# Un_Zigbee_V1_0.net
KiCad netlist of a schematic drawn in EAGLE
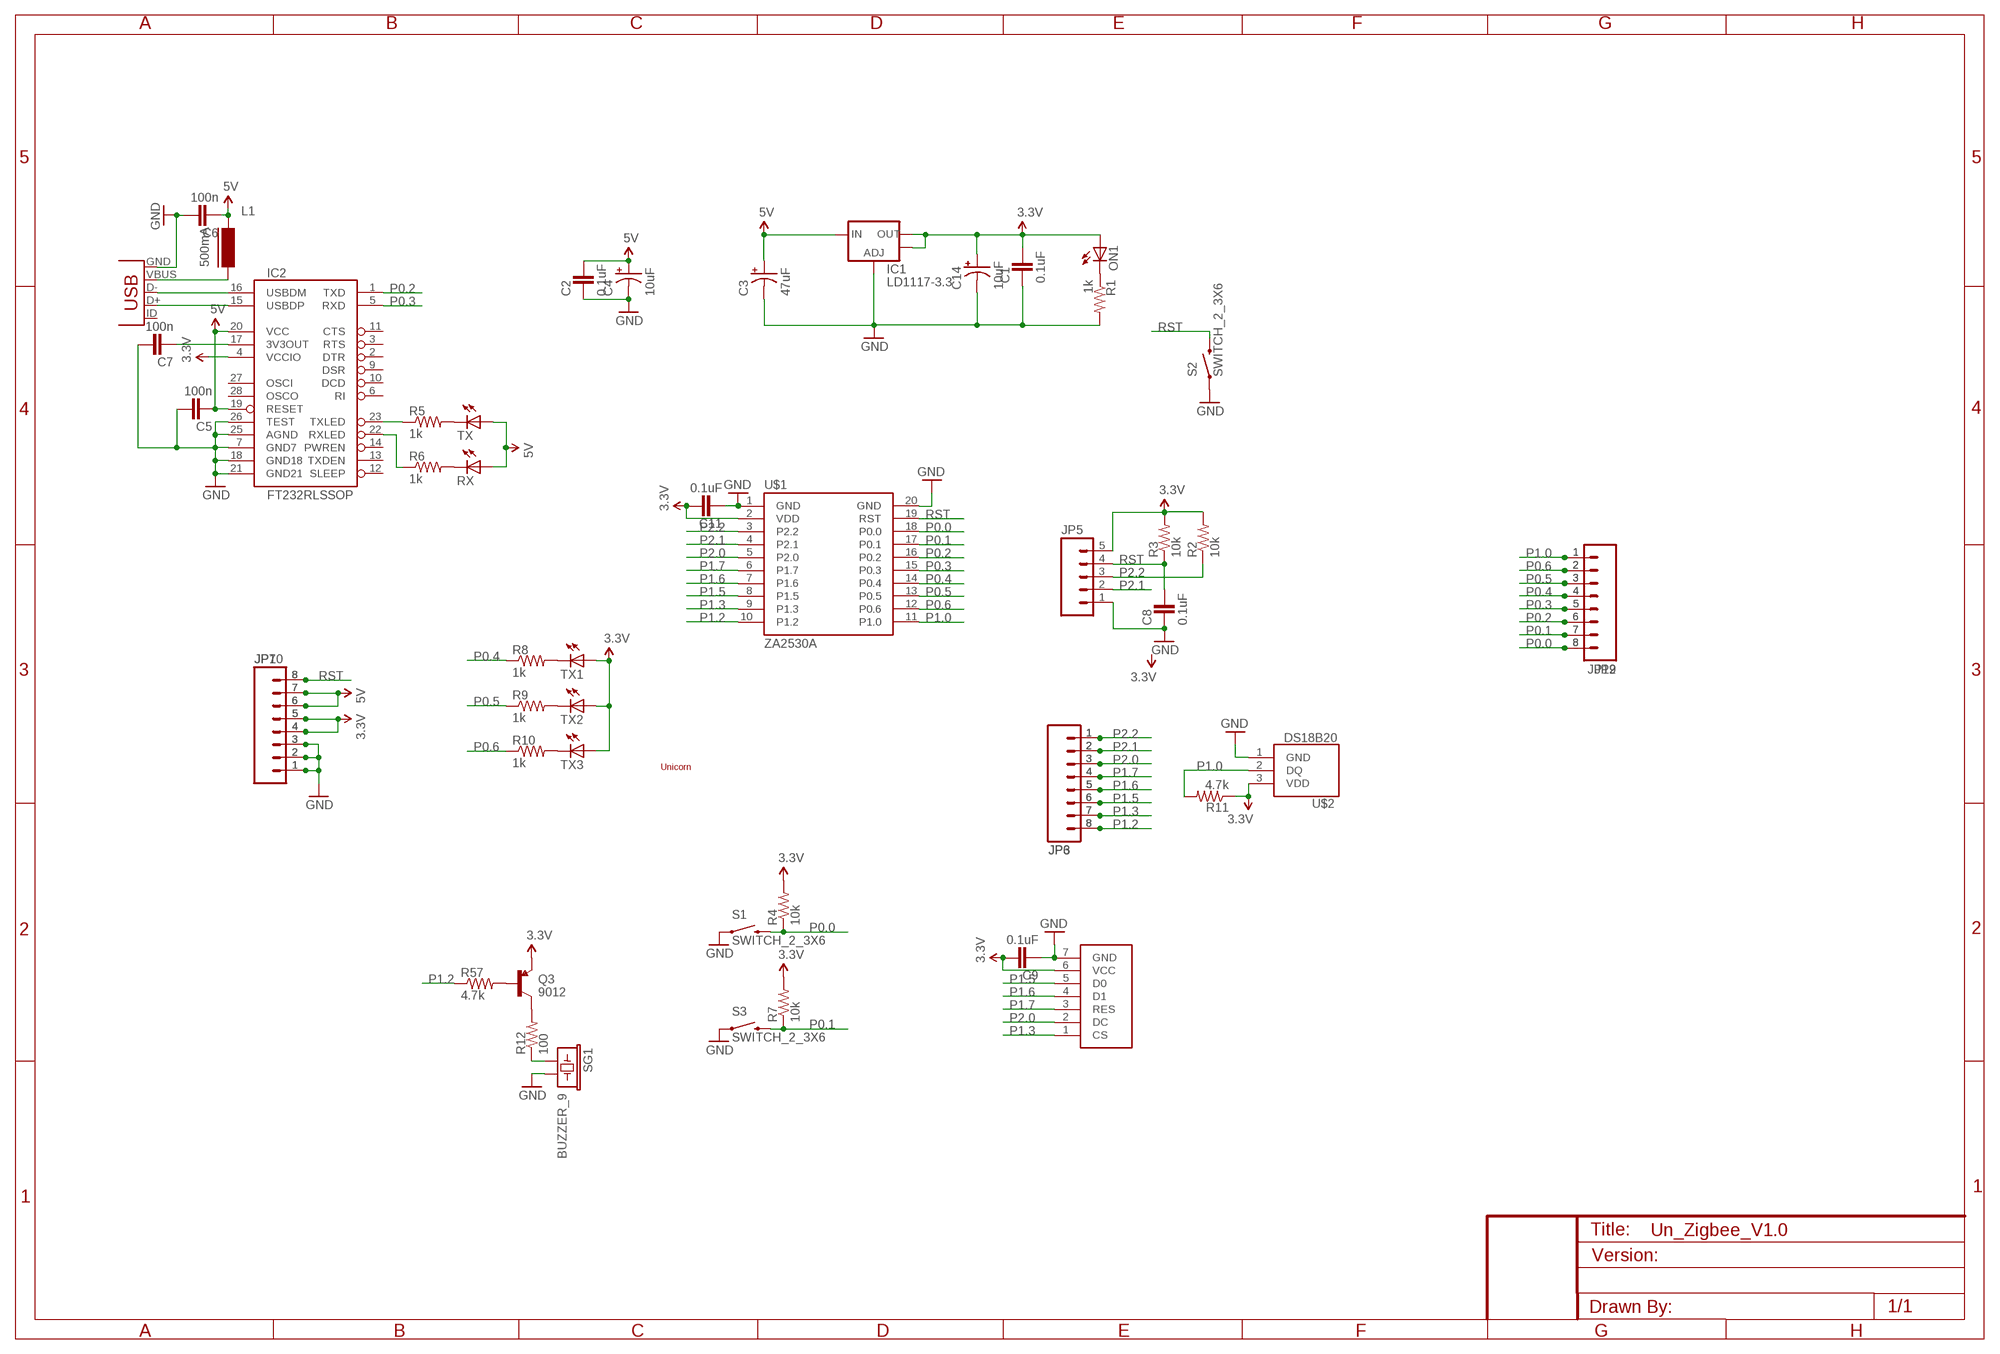
[diagram p0: schematic, sheet 1]

(export (version "E")
  (design (tool "Eeschema 10.0.6"))
  (components
    (comp (ref "C1")
      (value "0.1uF")
      (footprint "eagle-import:0603-CAP")
      (libsource (lib "eagle-import") (part "CAP0603"))
    )
    (comp (ref "C2")
      (value "0.1uF")
      (footprint "eagle-import:0603-CAP")
      (libsource (lib "eagle-import") (part "CAP0603"))
    )
    (comp (ref "C3")
      (value "47uF")
      (footprint "eagle-import:EIA3216")
      (libsource (lib "eagle-import") (part "CAP_POL1206"))
    )
    (comp (ref "C4")
      (value "10uF")
      (footprint "eagle-import:EIA3216")
      (libsource (lib "eagle-import") (part "CAP_POL1206"))
    )
    (comp (ref "C5")
      (value "100n")
      (footprint "eagle-import:0603-CAP")
      (libsource (lib "eagle-import") (part "CAP0603"))
    )
    (comp (ref "C6")
      (value "100n")
      (footprint "eagle-import:0603-CAP")
      (libsource (lib "eagle-import") (part "CAP0603"))
    )
    (comp (ref "C7")
      (value "100n")
      (footprint "eagle-import:0603-CAP")
      (libsource (lib "eagle-import") (part "CAP0603"))
    )
    (comp (ref "C8")
      (value "0.1uF")
      (footprint "eagle-import:0603-CAP")
      (libsource (lib "eagle-import") (part "CAP0603"))
    )
    (comp (ref "C9")
      (value "0.1uF")
      (footprint "eagle-import:0603-CAP")
      (libsource (lib "eagle-import") (part "CAP0603"))
    )
    (comp (ref "C11")
      (value "0.1uF")
      (footprint "eagle-import:0603-CAP")
      (libsource (lib "eagle-import") (part "CAP0603"))
    )
    (comp (ref "C14")
      (value "10uF")
      (footprint "eagle-import:EIA3216")
      (libsource (lib "eagle-import") (part "CAP_POL1206"))
    )
    (comp (ref "IC1")
      (value "LD1117-3.3")
      (footprint "eagle-import:SOT223")
      (libsource (lib "eagle-import") (part "V_REG_LM1117SOT223"))
    )
    (comp (ref "IC2")
      (value "FT232RLSSOP")
      (footprint "eagle-import:SSOP28DB")
      (libsource (lib "eagle-import") (part "FT232RLSSOP"))
    )
    (comp (ref "JP3")
      (value "M08")
      (footprint "eagle-import:1X08")
      (libsource (lib "eagle-import") (part "M08"))
    )
    (comp (ref "JP5")
      (value "M05PTH")
      (footprint "eagle-import:1X05")
      (libsource (lib "eagle-import") (part "M05PTH"))
    )
    (comp (ref "JP6")
      (value "M08")
      (footprint "eagle-import:1X08")
      (libsource (lib "eagle-import") (part "M08"))
    )
    (comp (ref "JP7")
      (value "M08")
      (footprint "eagle-import:1X08")
      (libsource (lib "eagle-import") (part "M08"))
    )
    (comp (ref "JP9")
      (value "M08")
      (footprint "eagle-import:1X08")
      (libsource (lib "eagle-import") (part "M08"))
    )
    (comp (ref "JP10")
      (value "M08")
      (footprint "eagle-import:1X08")
      (libsource (lib "eagle-import") (part "M08"))
    )
    (comp (ref "JP12")
      (value "M08")
      (footprint "eagle-import:1X08")
      (libsource (lib "eagle-import") (part "M08"))
    )
    (comp (ref "L1")
      (value "500mA")
      (footprint "eagle-import:FB805")
      (libsource (lib "eagle-import") (part "FERRITE-0805"))
    )
    (comp (ref "ON1")
      (value "LED0603")
      (footprint "eagle-import:LED-0603")
      (libsource (lib "eagle-import") (part "LED0603"))
    )
    (comp (ref "Q3")
      (value "9012")
      (footprint "eagle-import:SOT23-3")
      (libsource (lib "eagle-import") (part "TRANSISTOR_PNPSMD"))
    )
    (comp (ref "R1")
      (value "1k")
      (footprint "eagle-import:0603-RES")
      (libsource (lib "eagle-import") (part "RESISTOR0603-RES"))
    )
    (comp (ref "R2")
      (value "10k")
      (footprint "eagle-import:0603-RES")
      (libsource (lib "eagle-import") (part "RESISTOR0603-RES"))
    )
    (comp (ref "R3")
      (value "10k")
      (footprint "eagle-import:0603-RES")
      (libsource (lib "eagle-import") (part "RESISTOR0603-RES"))
    )
    (comp (ref "R4")
      (value "10k")
      (footprint "eagle-import:0603-RES")
      (libsource (lib "eagle-import") (part "RESISTOR0603-RES"))
    )
    (comp (ref "R5")
      (value "1k")
      (footprint "eagle-import:0603-RES")
      (libsource (lib "eagle-import") (part "RESISTOR0603-RES"))
    )
    (comp (ref "R6")
      (value "1k")
      (footprint "eagle-import:0603-RES")
      (libsource (lib "eagle-import") (part "RESISTOR0603-RES"))
    )
    (comp (ref "R7")
      (value "10k")
      (footprint "eagle-import:0603-RES")
      (libsource (lib "eagle-import") (part "RESISTOR0603-RES"))
    )
    (comp (ref "R8")
      (value "1k")
      (footprint "eagle-import:0603-RES")
      (libsource (lib "eagle-import") (part "RESISTOR0603-RES"))
    )
    (comp (ref "R9")
      (value "1k")
      (footprint "eagle-import:0603-RES")
      (libsource (lib "eagle-import") (part "RESISTOR0603-RES"))
    )
    (comp (ref "R10")
      (value "1k")
      (footprint "eagle-import:0603-RES")
      (libsource (lib "eagle-import") (part "RESISTOR0603-RES"))
    )
    (comp (ref "R11")
      (value "4.7k")
      (footprint "eagle-import:0603-RES")
      (libsource (lib "eagle-import") (part "RESISTOR0603-RES"))
    )
    (comp (ref "R12")
      (value "100")
      (footprint "eagle-import:0603-RES")
      (libsource (lib "eagle-import") (part "RESISTOR0603-RES"))
    )
    (comp (ref "R57")
      (value "4.7k")
      (footprint "eagle-import:0603-RES")
      (libsource (lib "eagle-import") (part "RESISTOR0603-RES"))
    )
    (comp (ref "RX")
      (value "LED0603")
      (footprint "eagle-import:LED-0603")
      (libsource (lib "eagle-import") (part "LED0603"))
    )
    (comp (ref "S1")
      (value "SWITCH_2_3X6")
      (footprint "eagle-import:TACTILE-SWITCH-1101NE")
      (libsource (lib "eagle-import") (part "SWITCH_2_3X6"))
    )
    (comp (ref "S2")
      (value "SWITCH_2_3X6")
      (footprint "eagle-import:TACTILE-SWITCH-1101NE")
      (libsource (lib "eagle-import") (part "SWITCH_2_3X6"))
    )
    (comp (ref "S3")
      (value "SWITCH_2_3X6")
      (footprint "eagle-import:TACTILE-SWITCH-1101NE")
      (libsource (lib "eagle-import") (part "SWITCH_2_3X6"))
    )
    (comp (ref "SG1")
      (value "BUZZER_9")
      (footprint "eagle-import:BUZZER-9MM")
      (libsource (lib "eagle-import") (part "BUZZER_9"))
    )
    (comp (ref "TX")
      (value "LED0603")
      (footprint "eagle-import:LED-0603")
      (libsource (lib "eagle-import") (part "LED0603"))
    )
    (comp (ref "TX1")
      (value "LED0603")
      (footprint "eagle-import:LED-0603")
      (libsource (lib "eagle-import") (part "LED0603"))
    )
    (comp (ref "TX2")
      (value "LED0603")
      (footprint "eagle-import:LED-0603")
      (libsource (lib "eagle-import") (part "LED0603"))
    )
    (comp (ref "TX3")
      (value "LED0603")
      (footprint "eagle-import:LED-0603")
      (libsource (lib "eagle-import") (part "LED0603"))
    )
    (comp (ref "U$1")
      (value "ZA2530A")
      (footprint "eagle-import:ZA2530A")
      (libsource (lib "eagle-import") (part "ZA2530A"))
    )
    (comp (ref "U$2")
      (value "DS18B20")
      (footprint "eagle-import:TO-92")
      (libsource (lib "eagle-import") (part "DS18B20"))
    )
    (comp (ref "U$3")
      (value "UNICORN_1")
      (footprint "eagle-import:UNICORN_1")
      (libsource (lib "eagle-import") (part "UNICORN_1"))
    )
    (comp (ref "U$7")
      (value "OLED_2")
      (footprint "eagle-import:OLED_2")
      (libsource (lib "eagle-import") (part "OLED_2"))
    )
    (comp (ref "U$10")
      (value "USB_5-SMD")
      (footprint "eagle-import:USB-MINIB")
      (libsource (lib "eagle-import") (part "USB_5-SMD"))
    )
  )
  (nets
    (net (code "1") (name "/P0.0") (class "Default")
      (node (ref "JP12") (pin "8") (pinfunction "8_8") (pintype "passive"))
      (node (ref "JP9") (pin "8") (pinfunction "8_8") (pintype "passive"))
      (node (ref "R4") (pin "1") (pinfunction "1_1") (pintype "passive"))
      (node (ref "S1") (pin "P$2") (pinfunction "2_P$2") (pintype "passive"))
      (node (ref "U$1") (pin "18") (pinfunction "P0.0_18") (pintype "bidirectional"))
    )
    (net (code "2") (name "/P0.1") (class "Default")
      (node (ref "JP12") (pin "7") (pinfunction "7_7") (pintype "passive"))
      (node (ref "JP9") (pin "7") (pinfunction "7_7") (pintype "passive"))
      (node (ref "R7") (pin "1") (pinfunction "1_1") (pintype "passive"))
      (node (ref "S3") (pin "P$2") (pinfunction "2_P$2") (pintype "passive"))
      (node (ref "U$1") (pin "17") (pinfunction "P0.1_17") (pintype "bidirectional"))
    )
    (net (code "3") (name "/P0.2") (class "Default")
      (node (ref "IC2") (pin "1") (pinfunction "TXD_1") (pintype "output"))
      (node (ref "JP12") (pin "6") (pinfunction "6_6") (pintype "passive"))
      (node (ref "JP9") (pin "6") (pinfunction "6_6") (pintype "passive"))
      (node (ref "U$1") (pin "16") (pinfunction "P0.2_16") (pintype "bidirectional"))
    )
    (net (code "4") (name "/P0.3") (class "Default")
      (node (ref "IC2") (pin "5") (pinfunction "RXD_5") (pintype "input"))
      (node (ref "JP12") (pin "5") (pinfunction "5_5") (pintype "passive"))
      (node (ref "JP9") (pin "5") (pinfunction "5_5") (pintype "passive"))
      (node (ref "U$1") (pin "15") (pinfunction "P0.3_15") (pintype "bidirectional"))
    )
    (net (code "5") (name "/P0.4") (class "Default")
      (node (ref "JP12") (pin "4") (pinfunction "4_4") (pintype "passive"))
      (node (ref "JP9") (pin "4") (pinfunction "4_4") (pintype "passive"))
      (node (ref "R8") (pin "1") (pinfunction "1_1") (pintype "passive"))
      (node (ref "U$1") (pin "14") (pinfunction "P0.4_14") (pintype "bidirectional"))
    )
    (net (code "6") (name "/P0.5") (class "Default")
      (node (ref "JP12") (pin "3") (pinfunction "3_3") (pintype "passive"))
      (node (ref "JP9") (pin "3") (pinfunction "3_3") (pintype "passive"))
      (node (ref "R9") (pin "1") (pinfunction "1_1") (pintype "passive"))
      (node (ref "U$1") (pin "13") (pinfunction "P0.5_13") (pintype "bidirectional"))
    )
    (net (code "7") (name "/P0.6") (class "Default")
      (node (ref "JP12") (pin "2") (pinfunction "2_2") (pintype "passive"))
      (node (ref "JP9") (pin "2") (pinfunction "2_2") (pintype "passive"))
      (node (ref "R10") (pin "1") (pinfunction "1_1") (pintype "passive"))
      (node (ref "U$1") (pin "12") (pinfunction "P0.6_12") (pintype "bidirectional"))
    )
    (net (code "8") (name "/P1.0") (class "Default")
      (node (ref "JP12") (pin "1") (pinfunction "1_1") (pintype "passive"))
      (node (ref "JP9") (pin "1") (pinfunction "1_1") (pintype "passive"))
      (node (ref "R11") (pin "2") (pinfunction "2_2") (pintype "passive"))
      (node (ref "U$1") (pin "11") (pinfunction "P1.0_11") (pintype "bidirectional"))
      (node (ref "U$2") (pin "2") (pinfunction "DQ_2") (pintype "bidirectional"))
    )
    (net (code "9") (name "/P1.2") (class "Default")
      (node (ref "JP3") (pin "8") (pinfunction "8_8") (pintype "passive"))
      (node (ref "JP6") (pin "8") (pinfunction "8_8") (pintype "passive"))
      (node (ref "R57") (pin "1") (pinfunction "1_1") (pintype "passive"))
      (node (ref "U$1") (pin "10") (pinfunction "P1.2_10") (pintype "bidirectional"))
    )
    (net (code "10") (name "/P1.3") (class "Default")
      (node (ref "JP3") (pin "7") (pinfunction "7_7") (pintype "passive"))
      (node (ref "JP6") (pin "7") (pinfunction "7_7") (pintype "passive"))
      (node (ref "U$1") (pin "9") (pinfunction "P1.3_9") (pintype "bidirectional"))
      (node (ref "U$7") (pin "1") (pinfunction "CS_1") (pintype "bidirectional"))
    )
    (net (code "11") (name "/P1.5") (class "Default")
      (node (ref "JP3") (pin "6") (pinfunction "6_6") (pintype "passive"))
      (node (ref "JP6") (pin "6") (pinfunction "6_6") (pintype "passive"))
      (node (ref "U$1") (pin "8") (pinfunction "P1.5_8") (pintype "bidirectional"))
      (node (ref "U$7") (pin "5") (pinfunction "D0_5") (pintype "bidirectional"))
    )
    (net (code "12") (name "/P1.6") (class "Default")
      (node (ref "JP3") (pin "5") (pinfunction "5_5") (pintype "passive"))
      (node (ref "JP6") (pin "5") (pinfunction "5_5") (pintype "passive"))
      (node (ref "U$1") (pin "7") (pinfunction "P1.6_7") (pintype "bidirectional"))
      (node (ref "U$7") (pin "4") (pinfunction "D1_4") (pintype "bidirectional"))
    )
    (net (code "13") (name "/P1.7") (class "Default")
      (node (ref "JP3") (pin "4") (pinfunction "4_4") (pintype "passive"))
      (node (ref "JP6") (pin "4") (pinfunction "4_4") (pintype "passive"))
      (node (ref "U$1") (pin "6") (pinfunction "P1.7_6") (pintype "bidirectional"))
      (node (ref "U$7") (pin "3") (pinfunction "RES_3") (pintype "bidirectional"))
    )
    (net (code "14") (name "/P2.0") (class "Default")
      (node (ref "JP3") (pin "3") (pinfunction "3_3") (pintype "passive"))
      (node (ref "JP6") (pin "3") (pinfunction "3_3") (pintype "passive"))
      (node (ref "U$1") (pin "5") (pinfunction "P2.0_5") (pintype "bidirectional"))
      (node (ref "U$7") (pin "2") (pinfunction "DC_2") (pintype "bidirectional"))
    )
    (net (code "15") (name "/P2.1") (class "Default")
      (node (ref "JP3") (pin "2") (pinfunction "2_2") (pintype "passive"))
      (node (ref "JP5") (pin "2") (pinfunction "2_2") (pintype "passive"))
      (node (ref "JP6") (pin "2") (pinfunction "2_2") (pintype "passive"))
      (node (ref "U$1") (pin "4") (pinfunction "P2.1_4") (pintype "bidirectional"))
    )
    (net (code "16") (name "/P2.2") (class "Default")
      (node (ref "JP3") (pin "1") (pinfunction "1_1") (pintype "passive"))
      (node (ref "JP5") (pin "3") (pinfunction "3_3") (pintype "passive"))
      (node (ref "JP6") (pin "1") (pinfunction "1_1") (pintype "passive"))
      (node (ref "R2") (pin "1") (pinfunction "1_1") (pintype "passive"))
      (node (ref "U$1") (pin "3") (pinfunction "P2.2_3") (pintype "bidirectional"))
    )
    (net (code "17") (name "/RST") (class "Default")
      (node (ref "C8") (pin "1") (pinfunction "1_1") (pintype "passive"))
      (node (ref "JP10") (pin "8") (pinfunction "8_8") (pintype "passive"))
      (node (ref "JP5") (pin "4") (pinfunction "4_4") (pintype "passive"))
      (node (ref "JP7") (pin "8") (pinfunction "8_8") (pintype "passive"))
      (node (ref "R3") (pin "1") (pinfunction "1_1") (pintype "passive"))
      (node (ref "S2") (pin "P$2") (pinfunction "2_P$2") (pintype "passive"))
      (node (ref "U$1") (pin "19") (pinfunction "RST_19") (pintype "bidirectional"))
    )
    (net (code "18") (name "3.3V") (class "Default")
      (node (ref "C1") (pin "1") (pinfunction "1_1") (pintype "passive"))
      (node (ref "C11") (pin "1") (pinfunction "1_1") (pintype "passive"))
      (node (ref "C14") (pin "A") (pinfunction "+_A") (pintype "passive"))
      (node (ref "C9") (pin "1") (pinfunction "1_1") (pintype "passive"))
      (node (ref "IC1") (pin "2") (pinfunction "OUT_2") (pintype "output"))
      (node (ref "IC1") (pin "4") (pinfunction "OUT_4") (pintype "output"))
      (node (ref "IC2") (pin "4") (pinfunction "VCCIO_4") (pintype "power_in"))
      (node (ref "JP10") (pin "4") (pinfunction "4_4") (pintype "passive"))
      (node (ref "JP10") (pin "5") (pinfunction "5_5") (pintype "passive"))
      (node (ref "JP5") (pin "5") (pinfunction "5_5") (pintype "passive"))
      (node (ref "JP7") (pin "4") (pinfunction "4_4") (pintype "passive"))
      (node (ref "JP7") (pin "5") (pinfunction "5_5") (pintype "passive"))
      (node (ref "ON1") (pin "A") (pinfunction "A_A") (pintype "passive"))
      (node (ref "Q3") (pin "2") (pinfunction "E_2") (pintype "passive"))
      (node (ref "R11") (pin "1") (pinfunction "1_1") (pintype "passive"))
      (node (ref "R2") (pin "2") (pinfunction "2_2") (pintype "passive"))
      (node (ref "R3") (pin "2") (pinfunction "2_2") (pintype "passive"))
      (node (ref "R4") (pin "2") (pinfunction "2_2") (pintype "passive"))
      (node (ref "R7") (pin "2") (pinfunction "2_2") (pintype "passive"))
      (node (ref "TX1") (pin "A") (pinfunction "A_A") (pintype "passive"))
      (node (ref "TX2") (pin "A") (pinfunction "A_A") (pintype "passive"))
      (node (ref "TX3") (pin "A") (pinfunction "A_A") (pintype "passive"))
      (node (ref "U$1") (pin "2") (pinfunction "VDD_2") (pintype "bidirectional"))
      (node (ref "U$2") (pin "3") (pinfunction "VDD_3") (pintype "power_in"))
      (node (ref "U$7") (pin "6") (pinfunction "VCC_6") (pintype "power_in"))
    )
    (net (code "19") (name "5V") (class "Default")
      (node (ref "C2") (pin "1") (pinfunction "1_1") (pintype "passive"))
      (node (ref "C3") (pin "A") (pinfunction "+_A") (pintype "passive"))
      (node (ref "C4") (pin "A") (pinfunction "+_A") (pintype "passive"))
      (node (ref "C5") (pin "2") (pinfunction "2_2") (pintype "passive"))
      (node (ref "C6") (pin "2") (pinfunction "2_2") (pintype "passive"))
      (node (ref "IC1") (pin "3") (pinfunction "IN_3") (pintype "input"))
      (node (ref "IC2") (pin "19") (pinfunction "RESET_19") (pintype "input"))
      (node (ref "IC2") (pin "20") (pinfunction "VCC_20") (pintype "power_in"))
      (node (ref "JP10") (pin "6") (pinfunction "6_6") (pintype "passive"))
      (node (ref "JP10") (pin "7") (pinfunction "7_7") (pintype "passive"))
      (node (ref "JP7") (pin "6") (pinfunction "6_6") (pintype "passive"))
      (node (ref "JP7") (pin "7") (pinfunction "7_7") (pintype "passive"))
      (node (ref "L1") (pin "1") (pinfunction "1_1") (pintype "passive"))
      (node (ref "RX") (pin "A") (pinfunction "A_A") (pintype "passive"))
      (node (ref "TX") (pin "A") (pinfunction "A_A") (pintype "passive"))
    )
    (net (code "20") (name "GND") (class "Default")
      (node (ref "C1") (pin "2") (pinfunction "2_2") (pintype "passive"))
      (node (ref "C11") (pin "2") (pinfunction "2_2") (pintype "passive"))
      (node (ref "C14") (pin "C") (pinfunction "-_C") (pintype "passive"))
      (node (ref "C2") (pin "2") (pinfunction "2_2") (pintype "passive"))
      (node (ref "C3") (pin "C") (pinfunction "-_C") (pintype "passive"))
      (node (ref "C4") (pin "C") (pinfunction "-_C") (pintype "passive"))
      (node (ref "C5") (pin "1") (pinfunction "1_1") (pintype "passive"))
      (node (ref "C6") (pin "1") (pinfunction "1_1") (pintype "passive"))
      (node (ref "C7") (pin "1") (pinfunction "1_1") (pintype "passive"))
      (node (ref "C8") (pin "2") (pinfunction "2_2") (pintype "passive"))
      (node (ref "C9") (pin "2") (pinfunction "2_2") (pintype "passive"))
      (node (ref "IC1") (pin "1") (pinfunction "ADJ_1") (pintype "input"))
      (node (ref "IC2") (pin "18") (pinfunction "GND18_18") (pintype "power_in"))
      (node (ref "IC2") (pin "21") (pinfunction "GND21_21") (pintype "power_in"))
      (node (ref "IC2") (pin "25") (pinfunction "AGND_25") (pintype "power_in"))
      (node (ref "IC2") (pin "26") (pinfunction "TEST_26") (pintype "input"))
      (node (ref "IC2") (pin "7") (pinfunction "GND7_7") (pintype "power_in"))
      (node (ref "JP10") (pin "1") (pinfunction "1_1") (pintype "passive"))
      (node (ref "JP10") (pin "2") (pinfunction "2_2") (pintype "passive"))
      (node (ref "JP10") (pin "3") (pinfunction "3_3") (pintype "passive"))
      (node (ref "JP5") (pin "1") (pinfunction "1_1") (pintype "passive"))
      (node (ref "JP7") (pin "1") (pinfunction "1_1") (pintype "passive"))
      (node (ref "JP7") (pin "2") (pinfunction "2_2") (pintype "passive"))
      (node (ref "JP7") (pin "3") (pinfunction "3_3") (pintype "passive"))
      (node (ref "R1") (pin "2") (pinfunction "2_2") (pintype "passive"))
      (node (ref "S1") (pin "P$1") (pinfunction "1_P$1") (pintype "passive"))
      (node (ref "S2") (pin "P$1") (pinfunction "1_P$1") (pintype "passive"))
      (node (ref "S3") (pin "P$1") (pinfunction "1_P$1") (pintype "passive"))
      (node (ref "SG1") (pin "-") (pinfunction "2_-") (pintype "passive"))
      (node (ref "U$1") (pin "1") (pinfunction "GND_1") (pintype "bidirectional"))
      (node (ref "U$1") (pin "20") (pinfunction "GND_20") (pintype "bidirectional"))
      (node (ref "U$10") (pin "GND") (pinfunction "GND_GND") (pintype "bidirectional"))
      (node (ref "U$2") (pin "1") (pinfunction "GND_1") (pintype "power_in"))
      (node (ref "U$7") (pin "7") (pinfunction "GND_7") (pintype "power_in"))
    )
    (net (code "21") (name "Net-(IC2-3V3OUT)") (class "Default")
      (node (ref "C7") (pin "2") (pinfunction "2_2") (pintype "passive"))
      (node (ref "IC2") (pin "17") (pinfunction "3V3OUT_17") (pintype "output"))
    )
    (net (code "22") (name "Net-(IC2-RXLED)") (class "Default")
      (node (ref "IC2") (pin "22") (pinfunction "RXLED_22") (pintype "input"))
      (node (ref "R6") (pin "1") (pinfunction "1_1") (pintype "passive"))
    )
    (net (code "23") (name "Net-(IC2-TXLED)") (class "Default")
      (node (ref "IC2") (pin "23") (pinfunction "TXLED_23") (pintype "input"))
      (node (ref "R5") (pin "1") (pinfunction "1_1") (pintype "passive"))
    )
    (net (code "24") (name "Net-(IC2-USBDM)") (class "Default")
      (node (ref "IC2") (pin "16") (pinfunction "USBDM_16") (pintype "bidirectional"))
      (node (ref "U$10") (pin "D-") (pinfunction "D-_D-") (pintype "bidirectional"))
    )
    (net (code "25") (name "Net-(IC2-USBDP)") (class "Default")
      (node (ref "IC2") (pin "15") (pinfunction "USBDP_15") (pintype "bidirectional"))
      (node (ref "U$10") (pin "D+") (pinfunction "D+_D+") (pintype "bidirectional"))
    )
    (net (code "26") (name "Net-(L1-Pad2)") (class "Default")
      (node (ref "L1") (pin "2") (pinfunction "2_2") (pintype "passive"))
      (node (ref "U$10") (pin "VBUS") (pinfunction "VBUS_VBUS") (pintype "bidirectional"))
    )
    (net (code "27") (name "Net-(ON1-PadC)") (class "Default")
      (node (ref "ON1") (pin "C") (pinfunction "C_C") (pintype "passive"))
      (node (ref "R1") (pin "1") (pinfunction "1_1") (pintype "passive"))
    )
    (net (code "28") (name "Net-(Q3-B)") (class "Default")
      (node (ref "Q3") (pin "1") (pinfunction "B_1") (pintype "passive"))
      (node (ref "R57") (pin "2") (pinfunction "2_2") (pintype "passive"))
    )
    (net (code "29") (name "Net-(Q3-C)") (class "Default")
      (node (ref "Q3") (pin "3") (pinfunction "C_3") (pintype "passive"))
      (node (ref "R12") (pin "2") (pinfunction "2_2") (pintype "passive"))
    )
    (net (code "30") (name "Net-(R5-Pad2)") (class "Default")
      (node (ref "R5") (pin "2") (pinfunction "2_2") (pintype "passive"))
      (node (ref "TX") (pin "C") (pinfunction "C_C") (pintype "passive"))
    )
    (net (code "31") (name "Net-(R6-Pad2)") (class "Default")
      (node (ref "R6") (pin "2") (pinfunction "2_2") (pintype "passive"))
      (node (ref "RX") (pin "C") (pinfunction "C_C") (pintype "passive"))
    )
    (net (code "32") (name "Net-(R8-Pad2)") (class "Default")
      (node (ref "R8") (pin "2") (pinfunction "2_2") (pintype "passive"))
      (node (ref "TX1") (pin "C") (pinfunction "C_C") (pintype "passive"))
    )
    (net (code "33") (name "Net-(R9-Pad2)") (class "Default")
      (node (ref "R9") (pin "2") (pinfunction "2_2") (pintype "passive"))
      (node (ref "TX2") (pin "C") (pinfunction "C_C") (pintype "passive"))
    )
    (net (code "34") (name "Net-(R10-Pad2)") (class "Default")
      (node (ref "R10") (pin "2") (pinfunction "2_2") (pintype "passive"))
      (node (ref "TX3") (pin "C") (pinfunction "C_C") (pintype "passive"))
    )
    (net (code "35") (name "Net-(SG1-1)") (class "Default")
      (node (ref "R12") (pin "1") (pinfunction "1_1") (pintype "passive"))
      (node (ref "SG1") (pin "+") (pinfunction "1_+") (pintype "passive"))
    )
    (net (code "36") (name "unconnected-(IC2-CTS-Pad11)") (class "Default")
      (node (ref "IC2") (pin "11") (pinfunction "CTS_11") (pintype "input"))
    )
    (net (code "37") (name "unconnected-(IC2-DCD-Pad10)") (class "Default")
      (node (ref "IC2") (pin "10") (pinfunction "DCD_10") (pintype "input"))
    )
    (net (code "38") (name "unconnected-(IC2-DSR-Pad9)") (class "Default")
      (node (ref "IC2") (pin "9") (pinfunction "DSR_9") (pintype "input"))
    )
    (net (code "39") (name "unconnected-(IC2-DTR-Pad2)") (class "Default")
      (node (ref "IC2") (pin "2") (pinfunction "DTR_2") (pintype "output"))
    )
    (net (code "40") (name "unconnected-(IC2-OSCI-Pad27)") (class "Default")
      (node (ref "IC2") (pin "27") (pinfunction "OSCI_27") (pintype "input"))
    )
    (net (code "41") (name "unconnected-(IC2-OSCO-Pad28)") (class "Default")
      (node (ref "IC2") (pin "28") (pinfunction "OSCO_28") (pintype "output"))
    )
    (net (code "42") (name "unconnected-(IC2-PWREN-Pad14)") (class "Default")
      (node (ref "IC2") (pin "14") (pinfunction "PWREN_14") (pintype "input"))
    )
    (net (code "43") (name "unconnected-(IC2-RI-Pad6)") (class "Default")
      (node (ref "IC2") (pin "6") (pinfunction "RI_6") (pintype "input"))
    )
    (net (code "44") (name "unconnected-(IC2-RTS-Pad3)") (class "Default")
      (node (ref "IC2") (pin "3") (pinfunction "RTS_3") (pintype "output"))
    )
    (net (code "45") (name "unconnected-(IC2-SLEEP-Pad12)") (class "Default")
      (node (ref "IC2") (pin "12") (pinfunction "SLEEP_12") (pintype "input"))
    )
    (net (code "46") (name "unconnected-(IC2-TXDEN-Pad13)") (class "Default")
      (node (ref "IC2") (pin "13") (pinfunction "TXDEN_13") (pintype "input"))
    )
    (net (code "47") (name "unconnected-(U$10-USBID-PadID)") (class "Default")
      (node (ref "U$10") (pin "ID") (pinfunction "USBID_ID") (pintype "bidirectional"))
    )
  )
)
